# remote_v4.net
KiCad netlist of a schematic drawn in EAGLE
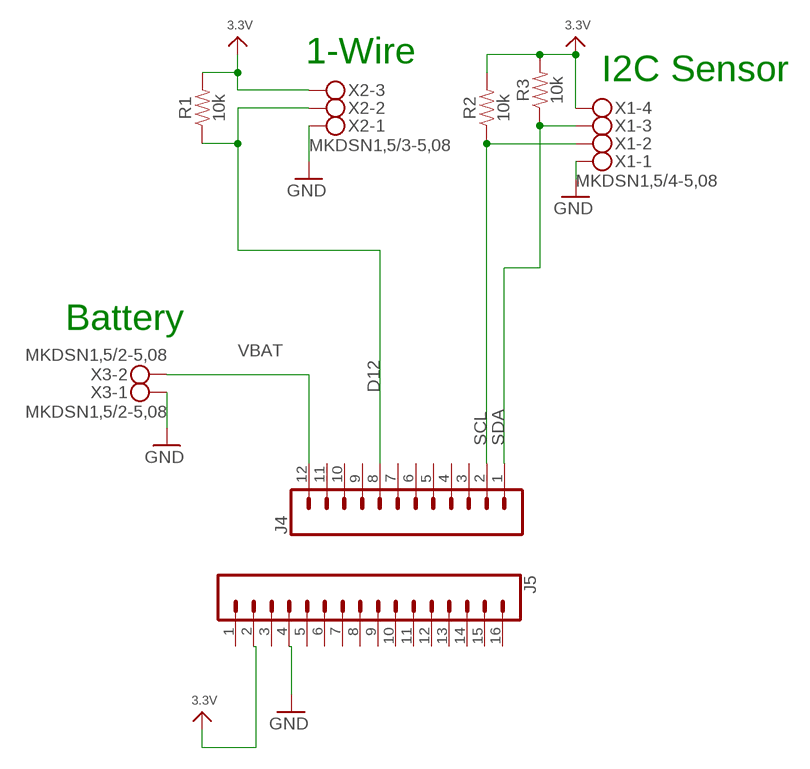
[diagram p0: schematic, sheet 1]

(export (version "E")
  (design (tool "Eeschema 10.0.6"))
  (components
    (comp (ref "J4")
      (value "CONN_12")
      (footprint "eagle-import:1X12")
      (libsource (lib "eagle-import") (part "CONN_12"))
    )
    (comp (ref "J5")
      (value "CONN_16")
      (footprint "eagle-import:1X16")
      (libsource (lib "eagle-import") (part "CONN_16"))
    )
    (comp (ref "R1")
      (value "10k")
      (footprint "eagle-import:AXIAL-0.3")
      (libsource (lib "eagle-import") (part "10KOHM-HORIZ-1/4W-1%"))
    )
    (comp (ref "R2")
      (value "10k")
      (footprint "eagle-import:AXIAL-0.3")
      (libsource (lib "eagle-import") (part "10KOHM-HORIZ-1/4W-1%"))
    )
    (comp (ref "R3")
      (value "10k")
      (footprint "eagle-import:AXIAL-0.3")
      (libsource (lib "eagle-import") (part "10KOHM-HORIZ-1/4W-1%"))
    )
    (comp (ref "X1")
      (value "MKDSN1,5/4-5,08")
      (footprint "eagle-import:MKDSN1,5_4-5,08")
      (libsource (lib "eagle-import") (part "MKDSN1,5/4-5,08"))
    )
    (comp (ref "X2")
      (value "MKDSN1,5/3-5,08")
      (footprint "eagle-import:MKDSN1,5_3-5,08")
      (libsource (lib "eagle-import") (part "MKDSN1,5/3-5,08"))
    )
    (comp (ref "X3")
      (value "MKDSN1,5/2-5,08")
      (footprint "eagle-import:MKDSN1,5_2-5,08")
      (libsource (lib "eagle-import") (part "MKDSN1,5/2-5,08"))
    )
  )
  (nets
    (net (code "1") (name "/D12") (class "Default")
      (node (ref "J4") (pin "8") (pinfunction "8_8") (pintype "passive"))
      (node (ref "R1") (pin "P$1") (pinfunction "1_P$1") (pintype "passive"))
      (node (ref "X2") (pin "2") (pinfunction "KL_2") (pintype "passive"))
    )
    (net (code "2") (name "/SCL") (class "Default")
      (node (ref "J4") (pin "2") (pinfunction "2_2") (pintype "passive"))
      (node (ref "R2") (pin "P$1") (pinfunction "1_P$1") (pintype "passive"))
      (node (ref "X1") (pin "2") (pinfunction "KL_2") (pintype "passive"))
    )
    (net (code "3") (name "/SDA") (class "Default")
      (node (ref "J4") (pin "1") (pinfunction "1_1") (pintype "passive"))
      (node (ref "R3") (pin "P$1") (pinfunction "1_P$1") (pintype "passive"))
      (node (ref "X1") (pin "3") (pinfunction "KL_3") (pintype "passive"))
    )
    (net (code "4") (name "/VBAT") (class "Default")
      (node (ref "J4") (pin "12") (pinfunction "12_12") (pintype "passive"))
      (node (ref "X3") (pin "2") (pinfunction "KL_2") (pintype "passive"))
    )
    (net (code "5") (name "3.3V") (class "Default")
      (node (ref "J5") (pin "2") (pinfunction "2_2") (pintype "passive"))
      (node (ref "R1") (pin "P$2") (pinfunction "2_P$2") (pintype "passive"))
      (node (ref "R2") (pin "P$2") (pinfunction "2_P$2") (pintype "passive"))
      (node (ref "R3") (pin "P$2") (pinfunction "2_P$2") (pintype "passive"))
      (node (ref "X1") (pin "4") (pinfunction "KL_4") (pintype "passive"))
      (node (ref "X2") (pin "3") (pinfunction "KL_3") (pintype "passive"))
    )
    (net (code "6") (name "GND") (class "Default")
      (node (ref "J5") (pin "4") (pinfunction "4_4") (pintype "passive"))
      (node (ref "X1") (pin "1") (pinfunction "KL_1") (pintype "passive"))
      (node (ref "X2") (pin "1") (pinfunction "KL_1") (pintype "passive"))
      (node (ref "X3") (pin "1") (pinfunction "KL_1") (pintype "passive"))
    )
    (net (code "7") (name "unconnected-(J4-Pad3)") (class "Default")
      (node (ref "J4") (pin "3") (pinfunction "3_3") (pintype "passive"))
    )
    (net (code "8") (name "unconnected-(J4-Pad4)") (class "Default")
      (node (ref "J4") (pin "4") (pinfunction "4_4") (pintype "passive"))
    )
    (net (code "9") (name "unconnected-(J4-Pad5)") (class "Default")
      (node (ref "J4") (pin "5") (pinfunction "5_5") (pintype "passive"))
    )
    (net (code "10") (name "unconnected-(J4-Pad6)") (class "Default")
      (node (ref "J4") (pin "6") (pinfunction "6_6") (pintype "passive"))
    )
    (net (code "11") (name "unconnected-(J4-Pad7)") (class "Default")
      (node (ref "J4") (pin "7") (pinfunction "7_7") (pintype "passive"))
    )
    (net (code "12") (name "unconnected-(J4-Pad9)") (class "Default")
      (node (ref "J4") (pin "9") (pinfunction "9_9") (pintype "passive"))
    )
    (net (code "13") (name "unconnected-(J4-Pad10)") (class "Default")
      (node (ref "J4") (pin "10") (pinfunction "10_10") (pintype "passive"))
    )
    (net (code "14") (name "unconnected-(J4-Pad11)") (class "Default")
      (node (ref "J4") (pin "11") (pinfunction "11_11") (pintype "passive"))
    )
    (net (code "15") (name "unconnected-(J5-Pad1)") (class "Default")
      (node (ref "J5") (pin "1") (pinfunction "1_1") (pintype "passive"))
    )
    (net (code "16") (name "unconnected-(J5-Pad3)") (class "Default")
      (node (ref "J5") (pin "3") (pinfunction "3_3") (pintype "passive"))
    )
    (net (code "17") (name "unconnected-(J5-Pad5)") (class "Default")
      (node (ref "J5") (pin "5") (pinfunction "5_5") (pintype "passive"))
    )
    (net (code "18") (name "unconnected-(J5-Pad6)") (class "Default")
      (node (ref "J5") (pin "6") (pinfunction "6_6") (pintype "passive"))
    )
    (net (code "19") (name "unconnected-(J5-Pad7)") (class "Default")
      (node (ref "J5") (pin "7") (pinfunction "7_7") (pintype "passive"))
    )
    (net (code "20") (name "unconnected-(J5-Pad8)") (class "Default")
      (node (ref "J5") (pin "8") (pinfunction "8_8") (pintype "passive"))
    )
    (net (code "21") (name "unconnected-(J5-Pad9)") (class "Default")
      (node (ref "J5") (pin "9") (pinfunction "9_9") (pintype "passive"))
    )
    (net (code "22") (name "unconnected-(J5-Pad10)") (class "Default")
      (node (ref "J5") (pin "10") (pinfunction "10_10") (pintype "passive"))
    )
    (net (code "23") (name "unconnected-(J5-Pad11)") (class "Default")
      (node (ref "J5") (pin "11") (pinfunction "11_11") (pintype "passive"))
    )
    (net (code "24") (name "unconnected-(J5-Pad12)") (class "Default")
      (node (ref "J5") (pin "12") (pinfunction "12_12") (pintype "passive"))
    )
    (net (code "25") (name "unconnected-(J5-Pad13)") (class "Default")
      (node (ref "J5") (pin "13") (pinfunction "13_13") (pintype "passive"))
    )
    (net (code "26") (name "unconnected-(J5-Pad14)") (class "Default")
      (node (ref "J5") (pin "14") (pinfunction "14_14") (pintype "passive"))
    )
    (net (code "27") (name "unconnected-(J5-Pad15)") (class "Default")
      (node (ref "J5") (pin "15") (pinfunction "15_15") (pintype "passive"))
    )
    (net (code "28") (name "unconnected-(J5-Pad16)") (class "Default")
      (node (ref "J5") (pin "16") (pinfunction "16_16") (pintype "passive"))
    )
  )
)
